# Decode.net
KiCad netlist of a schematic drawn in Altium Designer
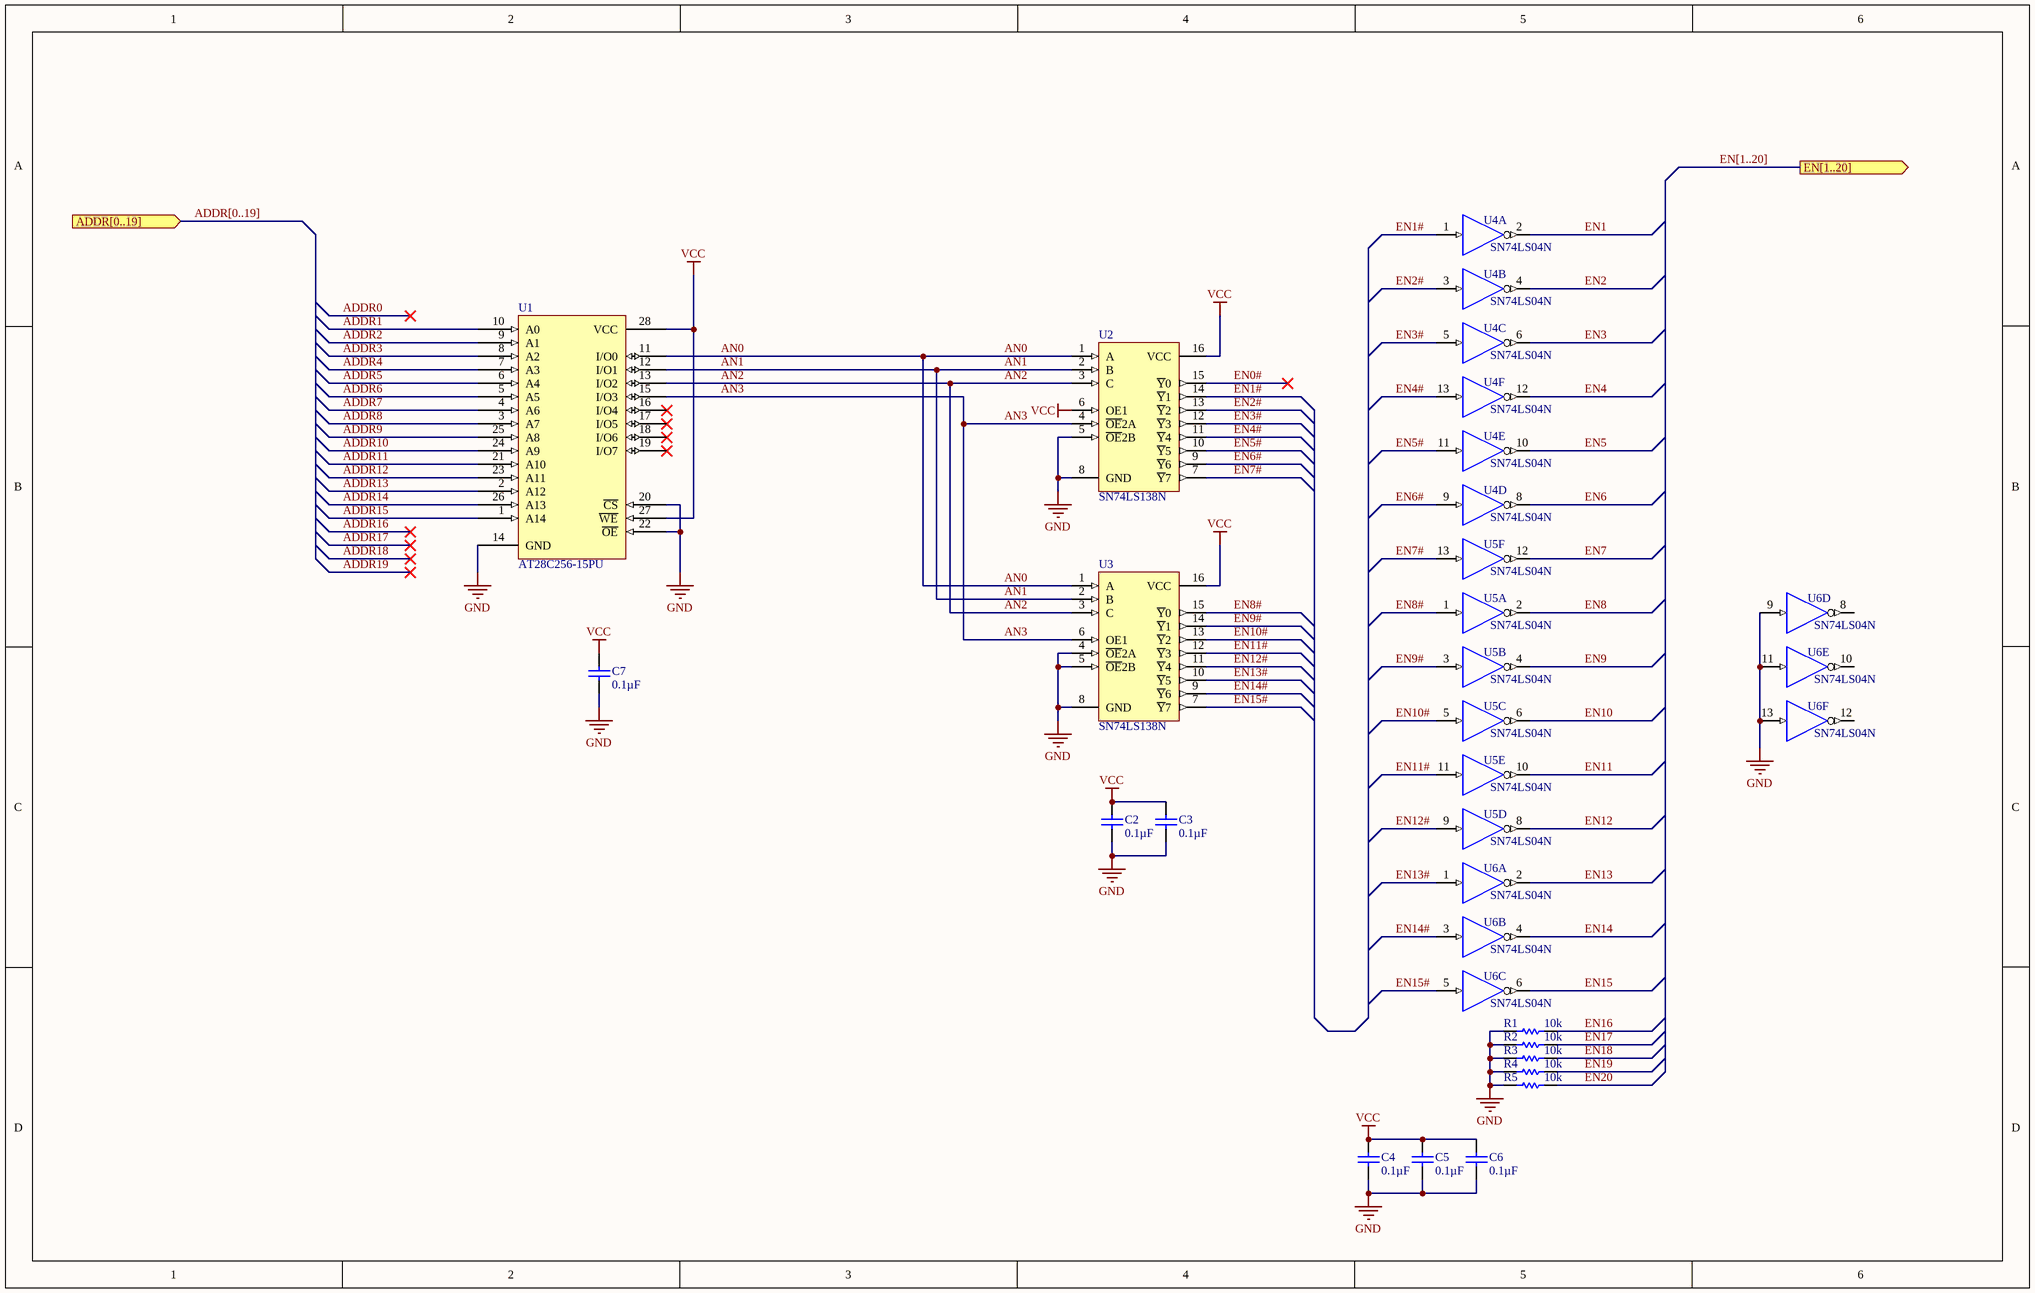
[diagram p0: Decode.SchDoc]

(export (version "E")
  (design (tool "Eeschema 10.0.6"))
  (components
    (comp (ref "C2")
      (value "K104K15X7RF5TL2")
      (footprint "VISH-K104K15X7RF5TL2")
      (description "Ceramic Capacitor, 100 nF, +/- 10%, 50 V, -55 to 125 degC, 2-Pin THD, RoHS, Tape and Reel")
      (fields
        (field (name "MANUFACTURER") "Vishay")
        (field (name "TOLERANCE") "±10%")
        (field (name "CAPACITANCE") "0.1µF")
      )
      (libsource (lib "Altium Content Vault") (part "CAP-NP-2"))
    )
    (comp (ref "C3")
      (value "K104K15X7RF5TL2")
      (footprint "VISH-K104K15X7RF5TL2")
      (description "Ceramic Capacitor, 100 nF, +/- 10%, 50 V, -55 to 125 degC, 2-Pin THD, RoHS, Tape and Reel")
      (fields
        (field (name "MANUFACTURER") "Vishay")
        (field (name "TOLERANCE") "±10%")
        (field (name "CAPACITANCE") "0.1µF")
      )
      (libsource (lib "Altium Content Vault") (part "CAP-NP-2"))
    )
    (comp (ref "C4")
      (value "K104K15X7RF5TL2")
      (footprint "VISH-K104K15X7RF5TL2")
      (description "Ceramic Capacitor, 100 nF, +/- 10%, 50 V, -55 to 125 degC, 2-Pin THD, RoHS, Tape and Reel")
      (fields
        (field (name "MANUFACTURER") "Vishay")
        (field (name "TOLERANCE") "±10%")
        (field (name "CAPACITANCE") "0.1µF")
      )
      (libsource (lib "Altium Content Vault") (part "CAP-NP-2"))
    )
    (comp (ref "C5")
      (value "K104K15X7RF5TL2")
      (footprint "VISH-K104K15X7RF5TL2")
      (description "Ceramic Capacitor, 100 nF, +/- 10%, 50 V, -55 to 125 degC, 2-Pin THD, RoHS, Tape and Reel")
      (fields
        (field (name "MANUFACTURER") "Vishay")
        (field (name "TOLERANCE") "±10%")
        (field (name "CAPACITANCE") "0.1µF")
      )
      (libsource (lib "Altium Content Vault") (part "CAP-NP-2"))
    )
    (comp (ref "C6")
      (value "K104K15X7RF5TL2")
      (footprint "VISH-K104K15X7RF5TL2")
      (description "Ceramic Capacitor, 100 nF, +/- 10%, 50 V, -55 to 125 degC, 2-Pin THD, RoHS, Tape and Reel")
      (fields
        (field (name "MANUFACTURER") "Vishay")
        (field (name "TOLERANCE") "±10%")
        (field (name "CAPACITANCE") "0.1µF")
      )
      (libsource (lib "Altium Content Vault") (part "CAP-NP-2"))
    )
    (comp (ref "C7")
      (value "K104K15X7RF5TL2")
      (footprint "VISH-K104K15X7RF5TL2")
      (description "Ceramic Capacitor, 100 nF, +/- 10%, 50 V, -55 to 125 degC, 2-Pin THD, RoHS, Tape and Reel")
      (fields
        (field (name "MANUFACTURER") "Vishay")
        (field (name "TOLERANCE") "±10%")
        (field (name "CAPACITANCE") "0.1µF")
      )
      (libsource (lib "Altium Content Vault") (part "CAP-NP-2"))
    )
    (comp (ref "R1")
      (value "10k")
      (footprint "AXIAL-0.3")
      (description "Resistor")
      (fields (field (name "Comment") "Res1") (field (name "PUBLISHER") "Altium Limited"))
      (libsource (lib "Miscellaneous Devices") (part "Res1"))
    )
    (comp (ref "R2")
      (value "10k")
      (footprint "AXIAL-0.3")
      (description "Resistor")
      (fields (field (name "Comment") "Res1") (field (name "PUBLISHER") "Altium Limited"))
      (libsource (lib "Miscellaneous Devices") (part "Res1"))
    )
    (comp (ref "R3")
      (value "10k")
      (footprint "AXIAL-0.3")
      (description "Resistor")
      (fields (field (name "Comment") "Res1") (field (name "PUBLISHER") "Altium Limited"))
      (libsource (lib "Miscellaneous Devices") (part "Res1"))
    )
    (comp (ref "R4")
      (value "10k")
      (footprint "AXIAL-0.3")
      (description "Resistor")
      (fields (field (name "Comment") "Res1") (field (name "PUBLISHER") "Altium Limited"))
      (libsource (lib "Miscellaneous Devices") (part "Res1"))
    )
    (comp (ref "R5")
      (value "10k")
      (footprint "AXIAL-0.3")
      (description "Resistor")
      (fields (field (name "Comment") "Res1") (field (name "PUBLISHER") "Altium Limited"))
      (libsource (lib "Miscellaneous Devices") (part "Res1"))
    )
    (comp (ref "U1")
      (value "AT28C256-15PU")
      (footprint "J028")
      (libsource (lib "Schlib1") (part "AT28C256-15PU"))
    )
    (comp (ref "U2")
      (value "SN74LS138N")
      (footprint "N016")
      (description "3-Line to 8-Line Decoder / Demultiplexer")
      (fields (field (name "PUBLISHER") "Altium Limited"))
      (libsource (lib "TI Logic Decoder Demux") (part "SN74LS138N"))
    )
    (comp (ref "U3")
      (value "SN74LS138N")
      (footprint "N016")
      (description "3-Line to 8-Line Decoder / Demultiplexer")
      (fields (field (name "PUBLISHER") "Altium Limited"))
      (libsource (lib "TI Logic Decoder Demux") (part "SN74LS138N"))
    )
    (comp (ref "U4")
      (value "SN74LS04N")
      (footprint "N014")
      (description "Hex Inverter")
      (fields (field (name "PUBLISHER") "Altium Limited"))
      (libsource (lib "TI Logic Gate 2") (part "SN74LS04N"))
    )
    (comp (ref "U5")
      (value "SN74LS04N")
      (footprint "N014")
      (description "Hex Inverter")
      (fields (field (name "PUBLISHER") "Altium Limited"))
      (libsource (lib "TI Logic Gate 2") (part "SN74LS04N"))
    )
    (comp (ref "U6")
      (value "SN74LS04N")
      (footprint "N014")
      (description "Hex Inverter")
      (fields (field (name "PUBLISHER") "Altium Limited"))
      (libsource (lib "TI Logic Gate 2") (part "SN74LS04N"))
    )
  )
  (nets
    (net (code "2") (name "/ADDR1") (class "Default")
      (node (ref "U1") (pin "10") (pinfunction "A0_10") (pintype "input"))
    )
    (net (code "3") (name "/ADDR2") (class "Default")
      (node (ref "U1") (pin "9") (pinfunction "A1_9") (pintype "input"))
    )
    (net (code "4") (name "/ADDR3") (class "Default")
      (node (ref "U1") (pin "8") (pinfunction "A2_8") (pintype "input"))
    )
    (net (code "5") (name "/ADDR4") (class "Default")
      (node (ref "U1") (pin "7") (pinfunction "A3_7") (pintype "input"))
    )
    (net (code "6") (name "/ADDR5") (class "Default")
      (node (ref "U1") (pin "6") (pinfunction "A4_6") (pintype "input"))
    )
    (net (code "7") (name "/ADDR6") (class "Default")
      (node (ref "U1") (pin "5") (pinfunction "A5_5") (pintype "input"))
    )
    (net (code "8") (name "/ADDR7") (class "Default")
      (node (ref "U1") (pin "4") (pinfunction "A6_4") (pintype "input"))
    )
    (net (code "9") (name "/ADDR8") (class "Default")
      (node (ref "U1") (pin "3") (pinfunction "A7_3") (pintype "input"))
    )
    (net (code "10") (name "/ADDR9") (class "Default")
      (node (ref "U1") (pin "25") (pinfunction "A8_25") (pintype "input"))
    )
    (net (code "11") (name "/ADDR10") (class "Default")
      (node (ref "U1") (pin "24") (pinfunction "A9_24") (pintype "input"))
    )
    (net (code "12") (name "/ADDR11") (class "Default")
      (node (ref "U1") (pin "21") (pinfunction "A10_21") (pintype "input"))
    )
    (net (code "13") (name "/ADDR12") (class "Default")
      (node (ref "U1") (pin "23") (pinfunction "A11_23") (pintype "input"))
    )
    (net (code "14") (name "/ADDR13") (class "Default")
      (node (ref "U1") (pin "2") (pinfunction "A12_2") (pintype "input"))
    )
    (net (code "15") (name "/ADDR14") (class "Default")
      (node (ref "U1") (pin "26") (pinfunction "A13_26") (pintype "input"))
    )
    (net (code "16") (name "/ADDR15") (class "Default")
      (node (ref "U1") (pin "1") (pinfunction "A14_1") (pintype "input"))
    )
    (net (code "22") (name "/AN0") (class "Default")
      (node (ref "U1") (pin "11") (pinfunction "I/O0_11") (pintype "bidirectional"))
      (node (ref "U2") (pin "1") (pinfunction "A_1") (pintype "input"))
      (node (ref "U3") (pin "1") (pinfunction "A_1") (pintype "input"))
    )
    (net (code "23") (name "/AN1") (class "Default")
      (node (ref "U1") (pin "12") (pinfunction "I/O1_12") (pintype "bidirectional"))
      (node (ref "U2") (pin "2") (pinfunction "B_2") (pintype "input"))
      (node (ref "U3") (pin "2") (pinfunction "B_2") (pintype "input"))
    )
    (net (code "24") (name "/AN2") (class "Default")
      (node (ref "U1") (pin "13") (pinfunction "I/O2_13") (pintype "bidirectional"))
      (node (ref "U2") (pin "3") (pinfunction "C_3") (pintype "input"))
      (node (ref "U3") (pin "3") (pinfunction "C_3") (pintype "input"))
    )
    (net (code "25") (name "/AN3") (class "Default")
      (node (ref "U1") (pin "15") (pinfunction "I/O3_15") (pintype "bidirectional"))
      (node (ref "U2") (pin "4") (pinfunction "~{OE}2A_4") (pintype "input"))
      (node (ref "U3") (pin "6") (pinfunction "OE1_6") (pintype "input"))
    )
    (net (code "26") (name "/EN0#") (class "Default")
      (node (ref "U2") (pin "15") (pinfunction "~{Y}0_15") (pintype "output+no_connect"))
    )
    (net (code "27") (name "/EN1") (class "Default")
      (node (ref "U4") (pin "2") (pinfunction "Y_2") (pintype "output"))
    )
    (net (code "28") (name "/EN1#") (class "Default")
      (node (ref "U2") (pin "14") (pinfunction "~{Y}1_14") (pintype "output"))
      (node (ref "U4") (pin "1") (pinfunction "A_1") (pintype "input"))
    )
    (net (code "29") (name "/EN2") (class "Default")
      (node (ref "U4") (pin "4") (pinfunction "Y_4") (pintype "output"))
    )
    (net (code "30") (name "/EN2#") (class "Default")
      (node (ref "U2") (pin "13") (pinfunction "~{Y}2_13") (pintype "output"))
      (node (ref "U4") (pin "3") (pinfunction "A_3") (pintype "input"))
    )
    (net (code "31") (name "/EN3") (class "Default")
      (node (ref "U4") (pin "6") (pinfunction "Y_6") (pintype "output"))
    )
    (net (code "32") (name "/EN3#") (class "Default")
      (node (ref "U2") (pin "12") (pinfunction "~{Y}3_12") (pintype "output"))
      (node (ref "U4") (pin "5") (pinfunction "A_5") (pintype "input"))
    )
    (net (code "33") (name "/EN4") (class "Default")
      (node (ref "U4") (pin "12") (pinfunction "Y_12") (pintype "output"))
    )
    (net (code "34") (name "/EN4#") (class "Default")
      (node (ref "U2") (pin "11") (pinfunction "~{Y}4_11") (pintype "output"))
      (node (ref "U4") (pin "13") (pinfunction "A_13") (pintype "input"))
    )
    (net (code "35") (name "/EN5") (class "Default")
      (node (ref "U4") (pin "10") (pinfunction "Y_10") (pintype "output"))
    )
    (net (code "36") (name "/EN5#") (class "Default")
      (node (ref "U2") (pin "10") (pinfunction "~{Y}5_10") (pintype "output"))
      (node (ref "U4") (pin "11") (pinfunction "A_11") (pintype "input"))
    )
    (net (code "37") (name "/EN6") (class "Default")
      (node (ref "U4") (pin "8") (pinfunction "Y_8") (pintype "output"))
    )
    (net (code "38") (name "/EN6#") (class "Default")
      (node (ref "U2") (pin "9") (pinfunction "~{Y}6_9") (pintype "output"))
      (node (ref "U4") (pin "9") (pinfunction "A_9") (pintype "input"))
    )
    (net (code "39") (name "/EN7") (class "Default")
      (node (ref "U5") (pin "12") (pinfunction "Y_12") (pintype "output"))
    )
    (net (code "40") (name "/EN7#") (class "Default")
      (node (ref "U2") (pin "7") (pinfunction "~{Y}7_7") (pintype "output"))
      (node (ref "U5") (pin "13") (pinfunction "A_13") (pintype "input"))
    )
    (net (code "41") (name "/EN8") (class "Default")
      (node (ref "U5") (pin "2") (pinfunction "Y_2") (pintype "output"))
    )
    (net (code "42") (name "/EN8#") (class "Default")
      (node (ref "U3") (pin "15") (pinfunction "~{Y}0_15") (pintype "output"))
      (node (ref "U5") (pin "1") (pinfunction "A_1") (pintype "input"))
    )
    (net (code "43") (name "/EN9") (class "Default")
      (node (ref "U5") (pin "4") (pinfunction "Y_4") (pintype "output"))
    )
    (net (code "44") (name "/EN9#") (class "Default")
      (node (ref "U3") (pin "14") (pinfunction "~{Y}1_14") (pintype "output"))
      (node (ref "U5") (pin "3") (pinfunction "A_3") (pintype "input"))
    )
    (net (code "45") (name "/EN10") (class "Default")
      (node (ref "U5") (pin "6") (pinfunction "Y_6") (pintype "output"))
    )
    (net (code "46") (name "/EN10#") (class "Default")
      (node (ref "U3") (pin "13") (pinfunction "~{Y}2_13") (pintype "output"))
      (node (ref "U5") (pin "5") (pinfunction "A_5") (pintype "input"))
    )
    (net (code "47") (name "/EN11") (class "Default")
      (node (ref "U5") (pin "10") (pinfunction "Y_10") (pintype "output"))
    )
    (net (code "48") (name "/EN11#") (class "Default")
      (node (ref "U3") (pin "12") (pinfunction "~{Y}3_12") (pintype "output"))
      (node (ref "U5") (pin "11") (pinfunction "A_11") (pintype "input"))
    )
    (net (code "49") (name "/EN12") (class "Default")
      (node (ref "U5") (pin "8") (pinfunction "Y_8") (pintype "output"))
    )
    (net (code "50") (name "/EN12#") (class "Default")
      (node (ref "U3") (pin "11") (pinfunction "~{Y}4_11") (pintype "output"))
      (node (ref "U5") (pin "9") (pinfunction "A_9") (pintype "input"))
    )
    (net (code "51") (name "/EN13") (class "Default")
      (node (ref "U6") (pin "2") (pinfunction "Y_2") (pintype "output"))
    )
    (net (code "52") (name "/EN13#") (class "Default")
      (node (ref "U3") (pin "10") (pinfunction "~{Y}5_10") (pintype "output"))
      (node (ref "U6") (pin "1") (pinfunction "A_1") (pintype "input"))
    )
    (net (code "53") (name "/EN14") (class "Default")
      (node (ref "U6") (pin "4") (pinfunction "Y_4") (pintype "output"))
    )
    (net (code "54") (name "/EN14#") (class "Default")
      (node (ref "U3") (pin "9") (pinfunction "~{Y}6_9") (pintype "output"))
      (node (ref "U6") (pin "3") (pinfunction "A_3") (pintype "input"))
    )
    (net (code "55") (name "/EN15") (class "Default")
      (node (ref "U6") (pin "6") (pinfunction "Y_6") (pintype "output"))
    )
    (net (code "56") (name "/EN15#") (class "Default")
      (node (ref "U3") (pin "7") (pinfunction "~{Y}7_7") (pintype "output"))
      (node (ref "U6") (pin "5") (pinfunction "A_5") (pintype "input"))
    )
    (net (code "57") (name "/EN16") (class "Default")
      (node (ref "R1") (pin "2") (pinfunction "2_2") (pintype "passive"))
    )
    (net (code "58") (name "/EN17") (class "Default")
      (node (ref "R2") (pin "2") (pinfunction "2_2") (pintype "passive"))
    )
    (net (code "59") (name "/EN18") (class "Default")
      (node (ref "R3") (pin "2") (pinfunction "2_2") (pintype "passive"))
    )
    (net (code "60") (name "/EN19") (class "Default")
      (node (ref "R4") (pin "2") (pinfunction "2_2") (pintype "passive"))
    )
    (net (code "61") (name "/EN20") (class "Default")
      (node (ref "R5") (pin "2") (pinfunction "2_2") (pintype "passive"))
    )
    (net (code "63") (name "GND") (class "Default")
      (node (ref "C2") (pin "2") (pinfunction "2_2") (pintype "passive"))
      (node (ref "C3") (pin "2") (pinfunction "2_2") (pintype "passive"))
      (node (ref "C4") (pin "2") (pinfunction "2_2") (pintype "passive"))
      (node (ref "C5") (pin "2") (pinfunction "2_2") (pintype "passive"))
      (node (ref "C6") (pin "2") (pinfunction "2_2") (pintype "passive"))
      (node (ref "C7") (pin "2") (pinfunction "2_2") (pintype "passive"))
      (node (ref "R1") (pin "1") (pinfunction "1_1") (pintype "passive"))
      (node (ref "R2") (pin "1") (pinfunction "1_1") (pintype "passive"))
      (node (ref "R3") (pin "1") (pinfunction "1_1") (pintype "passive"))
      (node (ref "R4") (pin "1") (pinfunction "1_1") (pintype "passive"))
      (node (ref "R5") (pin "1") (pinfunction "1_1") (pintype "passive"))
      (node (ref "U1") (pin "14") (pinfunction "GND_14") (pintype "power_in"))
      (node (ref "U1") (pin "20") (pinfunction "~{CS}_20") (pintype "input"))
      (node (ref "U1") (pin "22") (pinfunction "~{OE}_22") (pintype "input"))
      (node (ref "U2") (pin "5") (pinfunction "~{OE}2B_5") (pintype "input"))
      (node (ref "U2") (pin "8") (pinfunction "GND_8") (pintype "power_in"))
      (node (ref "U3") (pin "4") (pinfunction "~{OE}2A_4") (pintype "input"))
      (node (ref "U3") (pin "5") (pinfunction "~{OE}2B_5") (pintype "input"))
      (node (ref "U3") (pin "8") (pinfunction "GND_8") (pintype "power_in"))
      (node (ref "U4") (pin "7") (pinfunction "GND_7") (pintype "power_in"))
      (node (ref "U5") (pin "7") (pinfunction "GND_7") (pintype "power_in"))
      (node (ref "U6") (pin "11") (pinfunction "A_11") (pintype "input"))
      (node (ref "U6") (pin "13") (pinfunction "A_13") (pintype "input"))
      (node (ref "U6") (pin "7") (pinfunction "GND_7") (pintype "power_in"))
      (node (ref "U6") (pin "9") (pinfunction "A_9") (pintype "input"))
    )
    (net (code "64") (name "VCC") (class "Default")
      (node (ref "C2") (pin "1") (pinfunction "1_1") (pintype "passive"))
      (node (ref "C3") (pin "1") (pinfunction "1_1") (pintype "passive"))
      (node (ref "C4") (pin "1") (pinfunction "1_1") (pintype "passive"))
      (node (ref "C5") (pin "1") (pinfunction "1_1") (pintype "passive"))
      (node (ref "C6") (pin "1") (pinfunction "1_1") (pintype "passive"))
      (node (ref "C7") (pin "1") (pinfunction "1_1") (pintype "passive"))
      (node (ref "U1") (pin "27") (pinfunction "~{WE}_27") (pintype "input"))
      (node (ref "U1") (pin "28") (pinfunction "VCC_28") (pintype "power_in"))
      (node (ref "U2") (pin "16") (pinfunction "VCC_16") (pintype "power_in"))
      (node (ref "U2") (pin "6") (pinfunction "OE1_6") (pintype "input"))
      (node (ref "U3") (pin "16") (pinfunction "VCC_16") (pintype "power_in"))
      (node (ref "U4") (pin "14") (pinfunction "VCC_14") (pintype "power_in"))
      (node (ref "U5") (pin "14") (pinfunction "VCC_14") (pintype "power_in"))
      (node (ref "U6") (pin "14") (pinfunction "VCC_14") (pintype "power_in"))
    )
    (net (code "65") (name "unconnected-(U1-I{slash}O4-Pad16)") (class "Default")
      (node (ref "U1") (pin "16") (pinfunction "I/O4_16") (pintype "bidirectional+no_connect"))
    )
    (net (code "66") (name "unconnected-(U1-I{slash}O5-Pad17)") (class "Default")
      (node (ref "U1") (pin "17") (pinfunction "I/O5_17") (pintype "bidirectional+no_connect"))
    )
    (net (code "67") (name "unconnected-(U1-I{slash}O6-Pad18)") (class "Default")
      (node (ref "U1") (pin "18") (pinfunction "I/O6_18") (pintype "bidirectional+no_connect"))
    )
    (net (code "68") (name "unconnected-(U1-I{slash}O7-Pad19)") (class "Default")
      (node (ref "U1") (pin "19") (pinfunction "I/O7_19") (pintype "bidirectional+no_connect"))
    )
    (net (code "69") (name "unconnected-(U6D-Y-Pad8)") (class "Default")
      (node (ref "U6") (pin "8") (pinfunction "Y_8") (pintype "output"))
    )
    (net (code "70") (name "unconnected-(U6E-Y-Pad10)") (class "Default")
      (node (ref "U6") (pin "10") (pinfunction "Y_10") (pintype "output"))
    )
    (net (code "71") (name "unconnected-(U6F-Y-Pad12)") (class "Default")
      (node (ref "U6") (pin "12") (pinfunction "Y_12") (pintype "output"))
    )
  )
)
